# TeensyServoController.net
KiCad netlist of a schematic drawn in EAGLE
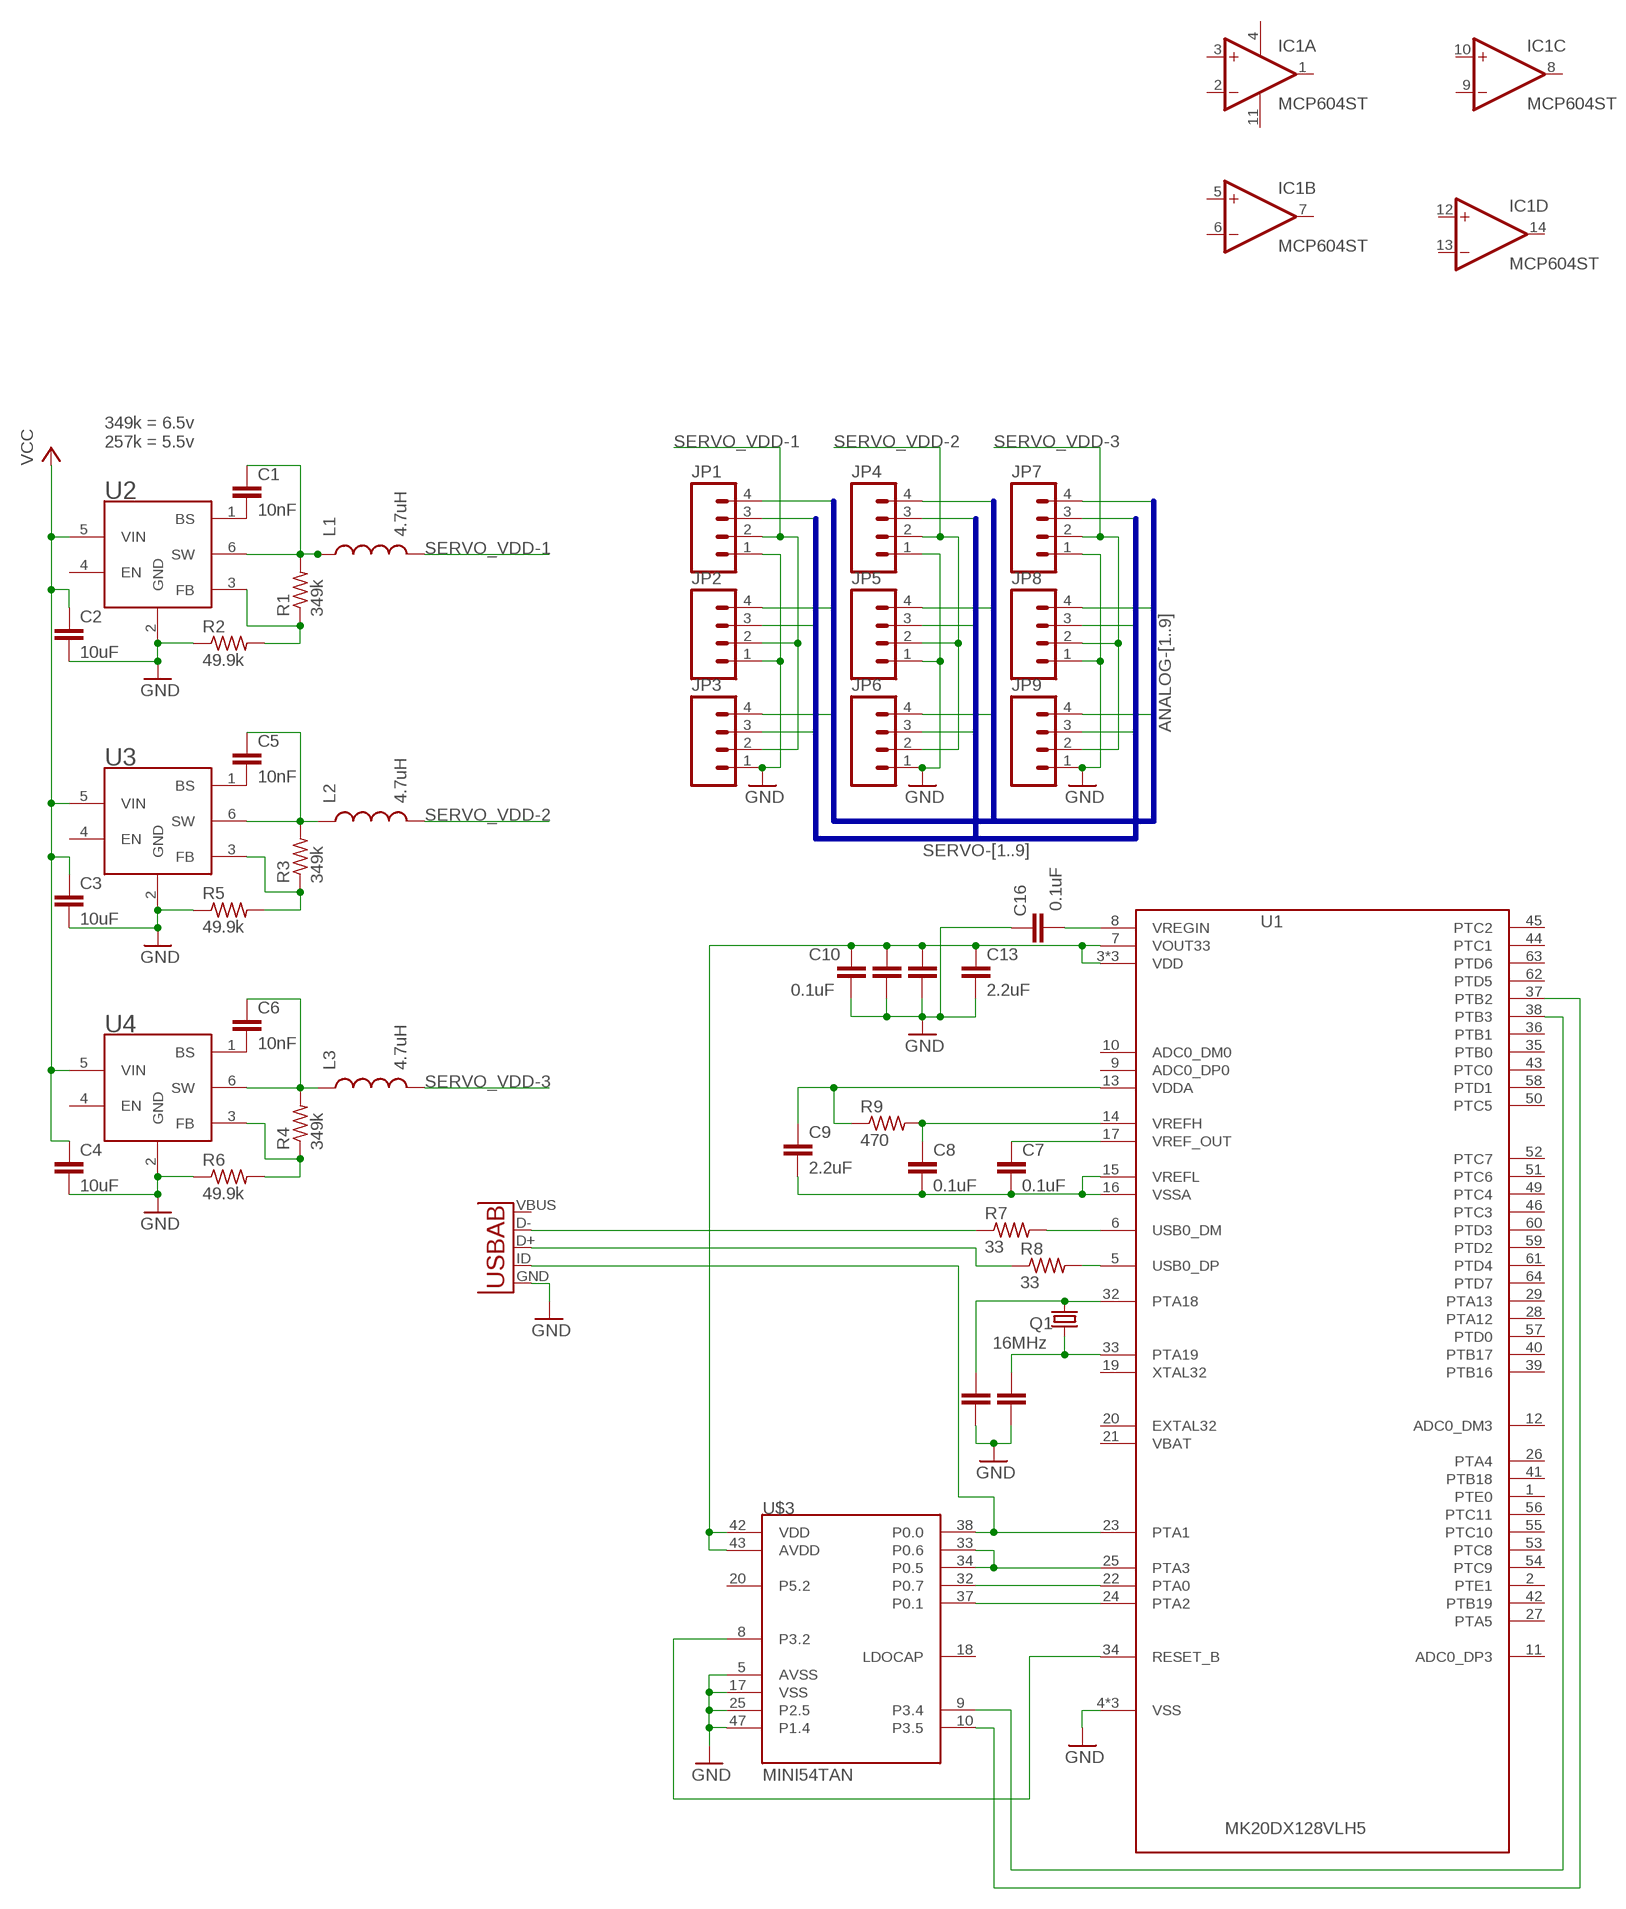
[diagram p0: schematic, sheet 1]

(export (version "E")
  (design (tool "Eeschema 10.0.6"))
  (components
    (comp (ref "C1")
      (value "10nF")
      (footprint "eagle-import:C0402")
      (libsource (lib "eagle-import") (part "C-EUC0402"))
    )
    (comp (ref "C2")
      (value "10uF")
      (footprint "eagle-import:C0805")
      (libsource (lib "eagle-import") (part "C-EUC0805"))
    )
    (comp (ref "C3")
      (value "10uF")
      (footprint "eagle-import:C0805")
      (libsource (lib "eagle-import") (part "C-EUC0805"))
    )
    (comp (ref "C4")
      (value "10uF")
      (footprint "eagle-import:C0805")
      (libsource (lib "eagle-import") (part "C-EUC0805"))
    )
    (comp (ref "C5")
      (value "10nF")
      (footprint "eagle-import:C0402")
      (libsource (lib "eagle-import") (part "C-EUC0402"))
    )
    (comp (ref "C6")
      (value "10nF")
      (footprint "eagle-import:C0402")
      (libsource (lib "eagle-import") (part "C-EUC0402"))
    )
    (comp (ref "C7")
      (value "0.1uF")
      (footprint "eagle-import:C0402")
      (libsource (lib "eagle-import") (part "C-EUC0402"))
    )
    (comp (ref "C8")
      (value "0.1uF")
      (footprint "eagle-import:C0402")
      (libsource (lib "eagle-import") (part "C-EUC0402"))
    )
    (comp (ref "C9")
      (value "2.2uF")
      (footprint "eagle-import:C0603")
      (libsource (lib "eagle-import") (part "C-EUC0603"))
    )
    (comp (ref "C10")
      (value "0.1uF")
      (footprint "eagle-import:C0402")
      (libsource (lib "eagle-import") (part "C-EUC0402"))
    )
    (comp (ref "C11")
      (value "0.1uF")
      (footprint "eagle-import:C0402")
      (libsource (lib "eagle-import") (part "C-EUC0402"))
    )
    (comp (ref "C12")
      (value "0.1uF")
      (footprint "eagle-import:C0402")
      (libsource (lib "eagle-import") (part "C-EUC0402"))
    )
    (comp (ref "C13")
      (value "2.2uF")
      (footprint "eagle-import:C0603")
      (libsource (lib "eagle-import") (part "C-EUC0603"))
    )
    (comp (ref "C14")
      (value "0.1uF")
      (footprint "eagle-import:C0402")
      (libsource (lib "eagle-import") (part "C-EUC0402"))
    )
    (comp (ref "C15")
      (value "0.1uF")
      (footprint "eagle-import:C0402")
      (libsource (lib "eagle-import") (part "C-EUC0402"))
    )
    (comp (ref "C16")
      (value "0.1uF")
      (footprint "eagle-import:C0402")
      (libsource (lib "eagle-import") (part "C-EUC0402"))
    )
    (comp (ref "IC1")
      (value "MCP604ST")
      (footprint "eagle-import:TSSOP14")
      (libsource (lib "eagle-import") (part "MCP604ST"))
    )
    (comp (ref "JP1")
      (value "M04LOCK")
      (footprint "eagle-import:1X04_LOCK")
      (libsource (lib "eagle-import") (part "M04LOCK"))
    )
    (comp (ref "JP2")
      (value "M04LOCK")
      (footprint "eagle-import:1X04_LOCK")
      (libsource (lib "eagle-import") (part "M04LOCK"))
    )
    (comp (ref "JP3")
      (value "M04LOCK")
      (footprint "eagle-import:1X04_LOCK")
      (libsource (lib "eagle-import") (part "M04LOCK"))
    )
    (comp (ref "JP4")
      (value "M04LOCK")
      (footprint "eagle-import:1X04_LOCK")
      (libsource (lib "eagle-import") (part "M04LOCK"))
    )
    (comp (ref "JP5")
      (value "M04LOCK")
      (footprint "eagle-import:1X04_LOCK")
      (libsource (lib "eagle-import") (part "M04LOCK"))
    )
    (comp (ref "JP6")
      (value "M04LOCK")
      (footprint "eagle-import:1X04_LOCK")
      (libsource (lib "eagle-import") (part "M04LOCK"))
    )
    (comp (ref "JP7")
      (value "M04LOCK")
      (footprint "eagle-import:1X04_LOCK")
      (libsource (lib "eagle-import") (part "M04LOCK"))
    )
    (comp (ref "JP8")
      (value "M04LOCK")
      (footprint "eagle-import:1X04_LOCK")
      (libsource (lib "eagle-import") (part "M04LOCK"))
    )
    (comp (ref "JP9")
      (value "M04LOCK")
      (footprint "eagle-import:1X04_LOCK")
      (libsource (lib "eagle-import") (part "M04LOCK"))
    )
    (comp (ref "L1")
      (value "4.7uH")
      (footprint "eagle-import:CR75")
      (libsource (lib "eagle-import") (part "INDUCTORCR75"))
    )
    (comp (ref "L2")
      (value "4.7uH")
      (footprint "eagle-import:CR75")
      (libsource (lib "eagle-import") (part "INDUCTORCR75"))
    )
    (comp (ref "L3")
      (value "4.7uH")
      (footprint "eagle-import:CR75")
      (libsource (lib "eagle-import") (part "INDUCTORCR75"))
    )
    (comp (ref "Q1")
      (value "16MHz")
      (footprint "eagle-import:CTS406")
      (libsource (lib "eagle-import") (part "CRYSTALCTS406"))
    )
    (comp (ref "R1")
      (value "349k")
      (footprint "eagle-import:R0402")
      (libsource (lib "eagle-import") (part "R-US_R0402"))
    )
    (comp (ref "R2")
      (value "49.9k")
      (footprint "eagle-import:R0402")
      (libsource (lib "eagle-import") (part "R-US_R0402"))
    )
    (comp (ref "R3")
      (value "349k")
      (footprint "eagle-import:R0402")
      (libsource (lib "eagle-import") (part "R-US_R0402"))
    )
    (comp (ref "R4")
      (value "349k")
      (footprint "eagle-import:R0402")
      (libsource (lib "eagle-import") (part "R-US_R0402"))
    )
    (comp (ref "R5")
      (value "49.9k")
      (footprint "eagle-import:R0402")
      (libsource (lib "eagle-import") (part "R-US_R0402"))
    )
    (comp (ref "R6")
      (value "49.9k")
      (footprint "eagle-import:R0402")
      (libsource (lib "eagle-import") (part "R-US_R0402"))
    )
    (comp (ref "R7")
      (value "33")
      (footprint "eagle-import:R0402")
      (libsource (lib "eagle-import") (part "R-US_R0402"))
    )
    (comp (ref "R8")
      (value "33")
      (footprint "eagle-import:R0402")
      (libsource (lib "eagle-import") (part "R-US_R0402"))
    )
    (comp (ref "R9")
      (value "470")
      (footprint "eagle-import:R0402")
      (libsource (lib "eagle-import") (part "R-US_R0402"))
    )
    (comp (ref "U$3")
      (value "MINI54TAN")
      (footprint "eagle-import:MINI54TAN")
      (libsource (lib "eagle-import") (part "MINI54TAN"))
    )
    (comp (ref "U1")
      (value "MK20DX128VLH5")
      (footprint "eagle-import:MK20DX128VLH5")
      (libsource (lib "eagle-import") (part "MK20DX128VLH5"))
    )
    (comp (ref "U2")
      (value "AP3211_SWITCHING_REGULATOR")
      (footprint "eagle-import:SOT-23-6")
      (libsource (lib "eagle-import") (part "AP3211_SWITCHING_REGULATOR"))
    )
    (comp (ref "U3")
      (value "AP3211_SWITCHING_REGULATOR")
      (footprint "eagle-import:SOT-23-6")
      (libsource (lib "eagle-import") (part "AP3211_SWITCHING_REGULATOR"))
    )
    (comp (ref "U4")
      (value "AP3211_SWITCHING_REGULATOR")
      (footprint "eagle-import:SOT-23-6")
      (libsource (lib "eagle-import") (part "AP3211_SWITCHING_REGULATOR"))
    )
    (comp (ref "U5")
      (value "USB-AB")
      (footprint "eagle-import:USB-AB-MICRO-SMD")
      (libsource (lib "eagle-import") (part "USB-AB"))
    )
  )
  (nets
    (net (code "21") (name "/SERVO_VDD-1") (class "Default")
      (node (ref "JP1") (pin "2") (pinfunction "2_2") (pintype "passive"))
      (node (ref "JP2") (pin "2") (pinfunction "2_2") (pintype "passive"))
      (node (ref "JP3") (pin "2") (pinfunction "2_2") (pintype "passive"))
      (node (ref "L1") (pin "P$2") (pinfunction "2_P$2") (pintype "passive"))
    )
    (net (code "22") (name "/SERVO_VDD-2") (class "Default")
      (node (ref "JP4") (pin "2") (pinfunction "2_2") (pintype "passive"))
      (node (ref "JP5") (pin "2") (pinfunction "2_2") (pintype "passive"))
      (node (ref "JP6") (pin "2") (pinfunction "2_2") (pintype "passive"))
      (node (ref "L2") (pin "P$2") (pinfunction "2_P$2") (pintype "passive"))
    )
    (net (code "23") (name "/SERVO_VDD-3") (class "Default")
      (node (ref "JP7") (pin "2") (pinfunction "2_2") (pintype "passive"))
      (node (ref "JP8") (pin "2") (pinfunction "2_2") (pintype "passive"))
      (node (ref "JP9") (pin "2") (pinfunction "2_2") (pintype "passive"))
      (node (ref "L3") (pin "P$2") (pinfunction "2_P$2") (pintype "passive"))
    )
    (net (code "24") (name "/V+") (class "Default")
      (node (ref "IC1") (pin "4") (pinfunction "V+_4") (pintype "power_in"))
    )
    (net (code "25") (name "/V-") (class "Default")
      (node (ref "IC1") (pin "11") (pinfunction "V-_11") (pintype "power_in"))
    )
    (net (code "26") (name "GND") (class "Default")
      (node (ref "C10") (pin "2") (pinfunction "2_2") (pintype "passive"))
      (node (ref "C11") (pin "2") (pinfunction "2_2") (pintype "passive"))
      (node (ref "C12") (pin "2") (pinfunction "2_2") (pintype "passive"))
      (node (ref "C13") (pin "2") (pinfunction "2_2") (pintype "passive"))
      (node (ref "C14") (pin "2") (pinfunction "2_2") (pintype "passive"))
      (node (ref "C15") (pin "2") (pinfunction "2_2") (pintype "passive"))
      (node (ref "C16") (pin "1") (pinfunction "1_1") (pintype "passive"))
      (node (ref "C2") (pin "2") (pinfunction "2_2") (pintype "passive"))
      (node (ref "C3") (pin "2") (pinfunction "2_2") (pintype "passive"))
      (node (ref "C4") (pin "2") (pinfunction "2_2") (pintype "passive"))
      (node (ref "JP1") (pin "1") (pinfunction "1_1") (pintype "passive"))
      (node (ref "JP2") (pin "1") (pinfunction "1_1") (pintype "passive"))
      (node (ref "JP3") (pin "1") (pinfunction "1_1") (pintype "passive"))
      (node (ref "JP4") (pin "1") (pinfunction "1_1") (pintype "passive"))
      (node (ref "JP5") (pin "1") (pinfunction "1_1") (pintype "passive"))
      (node (ref "JP6") (pin "1") (pinfunction "1_1") (pintype "passive"))
      (node (ref "JP7") (pin "1") (pinfunction "1_1") (pintype "passive"))
      (node (ref "JP8") (pin "1") (pinfunction "1_1") (pintype "passive"))
      (node (ref "JP9") (pin "1") (pinfunction "1_1") (pintype "passive"))
      (node (ref "R2") (pin "1") (pinfunction "1_1") (pintype "passive"))
      (node (ref "R5") (pin "1") (pinfunction "1_1") (pintype "passive"))
      (node (ref "R6") (pin "1") (pinfunction "1_1") (pintype "passive"))
      (node (ref "U$3") (pin "17") (pinfunction "VSS_17") (pintype "bidirectional"))
      (node (ref "U$3") (pin "25") (pinfunction "P2.5_25") (pintype "bidirectional"))
      (node (ref "U$3") (pin "47") (pinfunction "P1.4_47") (pintype "bidirectional"))
      (node (ref "U$3") (pin "5") (pinfunction "AVSS_5") (pintype "bidirectional"))
      (node (ref "U1") (pin "31") (pinfunction "VSS_31") (pintype "bidirectional"))
      (node (ref "U1") (pin "4") (pinfunction "VSS_4") (pintype "bidirectional"))
      (node (ref "U1") (pin "47") (pinfunction "VSS_47") (pintype "bidirectional"))
      (node (ref "U2") (pin "2") (pinfunction "GND_2") (pintype "bidirectional"))
      (node (ref "U3") (pin "2") (pinfunction "GND_2") (pintype "bidirectional"))
      (node (ref "U4") (pin "2") (pinfunction "GND_2") (pintype "bidirectional"))
      (node (ref "U5") (pin "GND") (pinfunction "GND_GND") (pintype "bidirectional"))
    )
    (net (code "27") (name "Net-(L1-1)") (class "Default")
      (node (ref "C1") (pin "1") (pinfunction "1_1") (pintype "passive"))
      (node (ref "L1") (pin "P$1") (pinfunction "1_P$1") (pintype "passive"))
      (node (ref "R1") (pin "2") (pinfunction "2_2") (pintype "passive"))
      (node (ref "U2") (pin "6") (pinfunction "SW_6") (pintype "bidirectional"))
    )
    (net (code "28") (name "Net-(L2-1)") (class "Default")
      (node (ref "C5") (pin "1") (pinfunction "1_1") (pintype "passive"))
      (node (ref "L2") (pin "P$1") (pinfunction "1_P$1") (pintype "passive"))
      (node (ref "R3") (pin "2") (pinfunction "2_2") (pintype "passive"))
      (node (ref "U3") (pin "6") (pinfunction "SW_6") (pintype "bidirectional"))
    )
    (net (code "29") (name "Net-(L3-1)") (class "Default")
      (node (ref "C6") (pin "1") (pinfunction "1_1") (pintype "passive"))
      (node (ref "L3") (pin "P$1") (pinfunction "1_P$1") (pintype "passive"))
      (node (ref "R4") (pin "2") (pinfunction "2_2") (pintype "passive"))
      (node (ref "U4") (pin "6") (pinfunction "SW_6") (pintype "bidirectional"))
    )
    (net (code "30") (name "Net-(Q1-2)") (class "Default")
      (node (ref "C14") (pin "1") (pinfunction "1_1") (pintype "passive"))
      (node (ref "Q1") (pin "3") (pinfunction "2_3") (pintype "passive"))
      (node (ref "U1") (pin "32") (pinfunction "PTA18_32") (pintype "bidirectional"))
    )
    (net (code "31") (name "Net-(R7-Pad1)") (class "Default")
      (node (ref "R7") (pin "1") (pinfunction "1_1") (pintype "passive"))
      (node (ref "U5") (pin "D-") (pinfunction "D-_D-") (pintype "bidirectional"))
    )
    (net (code "32") (name "Net-(R8-Pad1)") (class "Default")
      (node (ref "R8") (pin "1") (pinfunction "1_1") (pintype "passive"))
      (node (ref "U5") (pin "D+") (pinfunction "D+_D+") (pintype "bidirectional"))
    )
    (net (code "33") (name "Net-(U$3-AVDD)") (class "Default")
      (node (ref "C10") (pin "1") (pinfunction "1_1") (pintype "passive"))
      (node (ref "C11") (pin "1") (pinfunction "1_1") (pintype "passive"))
      (node (ref "C12") (pin "1") (pinfunction "1_1") (pintype "passive"))
      (node (ref "C13") (pin "1") (pinfunction "1_1") (pintype "passive"))
      (node (ref "U$3") (pin "42") (pinfunction "VDD_42") (pintype "bidirectional"))
      (node (ref "U$3") (pin "43") (pinfunction "AVDD_43") (pintype "bidirectional"))
      (node (ref "U1") (pin "3") (pinfunction "VDD_3") (pintype "bidirectional"))
      (node (ref "U1") (pin "30") (pinfunction "VDD_30") (pintype "bidirectional"))
      (node (ref "U1") (pin "48") (pinfunction "VDD_48") (pintype "bidirectional"))
      (node (ref "U1") (pin "7") (pinfunction "VOUT33_7") (pintype "bidirectional"))
    )
    (net (code "34") (name "Net-(U$3-P0.0)") (class "Default")
      (node (ref "U$3") (pin "38") (pinfunction "P0.0_38") (pintype "bidirectional"))
      (node (ref "U1") (pin "23") (pinfunction "PTA1_23") (pintype "bidirectional"))
      (node (ref "U5") (pin "ID") (pinfunction "USBID_ID") (pintype "bidirectional"))
    )
    (net (code "35") (name "Net-(U$3-P0.1)") (class "Default")
      (node (ref "U$3") (pin "37") (pinfunction "P0.1_37") (pintype "bidirectional"))
      (node (ref "U1") (pin "24") (pinfunction "PTA2_24") (pintype "bidirectional"))
    )
    (net (code "36") (name "Net-(U$3-P0.5)") (class "Default")
      (node (ref "U$3") (pin "33") (pinfunction "P0.6_33") (pintype "bidirectional"))
      (node (ref "U$3") (pin "34") (pinfunction "P0.5_34") (pintype "bidirectional"))
      (node (ref "U1") (pin "25") (pinfunction "PTA3_25") (pintype "bidirectional"))
    )
    (net (code "37") (name "Net-(U$3-P0.7)") (class "Default")
      (node (ref "U$3") (pin "32") (pinfunction "P0.7_32") (pintype "bidirectional"))
      (node (ref "U1") (pin "22") (pinfunction "PTA0_22") (pintype "bidirectional"))
    )
    (net (code "38") (name "Net-(U$3-P3.2)") (class "Default")
      (node (ref "U$3") (pin "8") (pinfunction "P3.2_8") (pintype "bidirectional"))
      (node (ref "U1") (pin "34") (pinfunction "RESET_B_34") (pintype "bidirectional"))
    )
    (net (code "39") (name "Net-(U$3-P3.4)") (class "Default")
      (node (ref "U$3") (pin "9") (pinfunction "P3.4_9") (pintype "bidirectional"))
      (node (ref "U1") (pin "38") (pinfunction "PTB3_38") (pintype "bidirectional"))
    )
    (net (code "40") (name "Net-(U$3-P3.5)") (class "Default")
      (node (ref "U$3") (pin "10") (pinfunction "P3.5_10") (pintype "bidirectional"))
      (node (ref "U1") (pin "37") (pinfunction "PTB2_37") (pintype "bidirectional"))
    )
    (net (code "41") (name "Net-(U1-PTA19)") (class "Default")
      (node (ref "C15") (pin "1") (pinfunction "1_1") (pintype "passive"))
      (node (ref "Q1") (pin "1") (pinfunction "1_1") (pintype "passive"))
      (node (ref "U1") (pin "33") (pinfunction "PTA19_33") (pintype "bidirectional"))
    )
    (net (code "42") (name "Net-(U1-USB0_DM)") (class "Default")
      (node (ref "R7") (pin "2") (pinfunction "2_2") (pintype "passive"))
      (node (ref "U1") (pin "6") (pinfunction "USB0_DM_6") (pintype "bidirectional"))
    )
    (net (code "43") (name "Net-(U1-USB0_DP)") (class "Default")
      (node (ref "R8") (pin "2") (pinfunction "2_2") (pintype "passive"))
      (node (ref "U1") (pin "5") (pinfunction "USB0_DP_5") (pintype "bidirectional"))
    )
    (net (code "44") (name "Net-(U1-VDDA)") (class "Default")
      (node (ref "C9") (pin "1") (pinfunction "1_1") (pintype "passive"))
      (node (ref "R9") (pin "1") (pinfunction "1_1") (pintype "passive"))
      (node (ref "U1") (pin "13") (pinfunction "VDDA_13") (pintype "bidirectional"))
    )
    (net (code "45") (name "Net-(U1-VREFH)") (class "Default")
      (node (ref "C8") (pin "1") (pinfunction "1_1") (pintype "passive"))
      (node (ref "R9") (pin "2") (pinfunction "2_2") (pintype "passive"))
      (node (ref "U1") (pin "14") (pinfunction "VREFH_14") (pintype "bidirectional"))
    )
    (net (code "46") (name "Net-(U1-VREFL)") (class "Default")
      (node (ref "C7") (pin "2") (pinfunction "2_2") (pintype "passive"))
      (node (ref "C8") (pin "2") (pinfunction "2_2") (pintype "passive"))
      (node (ref "C9") (pin "2") (pinfunction "2_2") (pintype "passive"))
      (node (ref "U1") (pin "15") (pinfunction "VREFL_15") (pintype "bidirectional"))
      (node (ref "U1") (pin "16") (pinfunction "VSSA_16") (pintype "bidirectional"))
    )
    (net (code "47") (name "Net-(U1-VREF_OUT)") (class "Default")
      (node (ref "C7") (pin "1") (pinfunction "1_1") (pintype "passive"))
      (node (ref "U1") (pin "17") (pinfunction "VREF_OUT_17") (pintype "bidirectional"))
    )
    (net (code "48") (name "Net-(U1-VREGIN)") (class "Default")
      (node (ref "C16") (pin "2") (pinfunction "2_2") (pintype "passive"))
      (node (ref "U1") (pin "8") (pinfunction "VREGIN_8") (pintype "bidirectional"))
    )
    (net (code "49") (name "Net-(U2-BS)") (class "Default")
      (node (ref "C1") (pin "2") (pinfunction "2_2") (pintype "passive"))
      (node (ref "U2") (pin "1") (pinfunction "BS_1") (pintype "bidirectional"))
    )
    (net (code "50") (name "Net-(U2-FB)") (class "Default")
      (node (ref "R1") (pin "1") (pinfunction "1_1") (pintype "passive"))
      (node (ref "R2") (pin "2") (pinfunction "2_2") (pintype "passive"))
      (node (ref "U2") (pin "3") (pinfunction "FB_3") (pintype "bidirectional"))
    )
    (net (code "51") (name "Net-(U3-BS)") (class "Default")
      (node (ref "C5") (pin "2") (pinfunction "2_2") (pintype "passive"))
      (node (ref "U3") (pin "1") (pinfunction "BS_1") (pintype "bidirectional"))
    )
    (net (code "52") (name "Net-(U3-FB)") (class "Default")
      (node (ref "R3") (pin "1") (pinfunction "1_1") (pintype "passive"))
      (node (ref "R5") (pin "2") (pinfunction "2_2") (pintype "passive"))
      (node (ref "U3") (pin "3") (pinfunction "FB_3") (pintype "bidirectional"))
    )
    (net (code "53") (name "Net-(U4-BS)") (class "Default")
      (node (ref "C6") (pin "2") (pinfunction "2_2") (pintype "passive"))
      (node (ref "U4") (pin "1") (pinfunction "BS_1") (pintype "bidirectional"))
    )
    (net (code "54") (name "Net-(U4-FB)") (class "Default")
      (node (ref "R4") (pin "1") (pinfunction "1_1") (pintype "passive"))
      (node (ref "R6") (pin "2") (pinfunction "2_2") (pintype "passive"))
      (node (ref "U4") (pin "3") (pinfunction "FB_3") (pintype "bidirectional"))
    )
    (net (code "55") (name "VCC") (class "Default")
      (node (ref "C2") (pin "1") (pinfunction "1_1") (pintype "passive"))
      (node (ref "C3") (pin "1") (pinfunction "1_1") (pintype "passive"))
      (node (ref "C4") (pin "1") (pinfunction "1_1") (pintype "passive"))
      (node (ref "U2") (pin "5") (pinfunction "VIN_5") (pintype "bidirectional"))
      (node (ref "U3") (pin "5") (pinfunction "VIN_5") (pintype "bidirectional"))
      (node (ref "U4") (pin "5") (pinfunction "VIN_5") (pintype "bidirectional"))
    )
    (net (code "56") (name "unconnected-(IC1A-+IN-Pad3)") (class "Default")
      (node (ref "IC1") (pin "3") (pinfunction "+IN_3") (pintype "input"))
    )
    (net (code "57") (name "unconnected-(IC1A--IN-Pad2)") (class "Default")
      (node (ref "IC1") (pin "2") (pinfunction "-IN_2") (pintype "input"))
    )
    (net (code "58") (name "unconnected-(IC1A-OUT-Pad1)") (class "Default")
      (node (ref "IC1") (pin "1") (pinfunction "OUT_1") (pintype "output"))
    )
    (net (code "59") (name "unconnected-(IC1B-+IN-Pad5)") (class "Default")
      (node (ref "IC1") (pin "5") (pinfunction "+IN_5") (pintype "input"))
    )
    (net (code "60") (name "unconnected-(IC1B--IN-Pad6)") (class "Default")
      (node (ref "IC1") (pin "6") (pinfunction "-IN_6") (pintype "input"))
    )
    (net (code "61") (name "unconnected-(IC1B-OUT-Pad7)") (class "Default")
      (node (ref "IC1") (pin "7") (pinfunction "OUT_7") (pintype "output"))
    )
    (net (code "62") (name "unconnected-(IC1C-+IN-Pad10)") (class "Default")
      (node (ref "IC1") (pin "10") (pinfunction "+IN_10") (pintype "input"))
    )
    (net (code "63") (name "unconnected-(IC1C--IN-Pad9)") (class "Default")
      (node (ref "IC1") (pin "9") (pinfunction "-IN_9") (pintype "input"))
    )
    (net (code "64") (name "unconnected-(IC1C-OUT-Pad8)") (class "Default")
      (node (ref "IC1") (pin "8") (pinfunction "OUT_8") (pintype "output"))
    )
    (net (code "65") (name "unconnected-(IC1D-+IN-Pad12)") (class "Default")
      (node (ref "IC1") (pin "12") (pinfunction "+IN_12") (pintype "input"))
    )
    (net (code "66") (name "unconnected-(IC1D--IN-Pad13)") (class "Default")
      (node (ref "IC1") (pin "13") (pinfunction "-IN_13") (pintype "input"))
    )
    (net (code "67") (name "unconnected-(IC1D-OUT-Pad14)") (class "Default")
      (node (ref "IC1") (pin "14") (pinfunction "OUT_14") (pintype "output"))
    )
    (net (code "68") (name "unconnected-(JP1-Pad3)") (class "Default")
      (node (ref "JP1") (pin "3") (pinfunction "3_3") (pintype "passive"))
    )
    (net (code "69") (name "unconnected-(JP1-Pad4)") (class "Default")
      (node (ref "JP1") (pin "4") (pinfunction "4_4") (pintype "passive"))
    )
    (net (code "70") (name "unconnected-(JP2-Pad3)") (class "Default")
      (node (ref "JP2") (pin "3") (pinfunction "3_3") (pintype "passive"))
    )
    (net (code "71") (name "unconnected-(JP2-Pad4)") (class "Default")
      (node (ref "JP2") (pin "4") (pinfunction "4_4") (pintype "passive"))
    )
    (net (code "72") (name "unconnected-(JP3-Pad3)") (class "Default")
      (node (ref "JP3") (pin "3") (pinfunction "3_3") (pintype "passive"))
    )
    (net (code "73") (name "unconnected-(JP3-Pad4)") (class "Default")
      (node (ref "JP3") (pin "4") (pinfunction "4_4") (pintype "passive"))
    )
    (net (code "74") (name "unconnected-(JP4-Pad3)") (class "Default")
      (node (ref "JP4") (pin "3") (pinfunction "3_3") (pintype "passive"))
    )
    (net (code "75") (name "unconnected-(JP4-Pad4)") (class "Default")
      (node (ref "JP4") (pin "4") (pinfunction "4_4") (pintype "passive"))
    )
    (net (code "76") (name "unconnected-(JP5-Pad3)") (class "Default")
      (node (ref "JP5") (pin "3") (pinfunction "3_3") (pintype "passive"))
    )
    (net (code "77") (name "unconnected-(JP5-Pad4)") (class "Default")
      (node (ref "JP5") (pin "4") (pinfunction "4_4") (pintype "passive"))
    )
    (net (code "78") (name "unconnected-(JP6-Pad3)") (class "Default")
      (node (ref "JP6") (pin "3") (pinfunction "3_3") (pintype "passive"))
    )
    (net (code "79") (name "unconnected-(JP6-Pad4)") (class "Default")
      (node (ref "JP6") (pin "4") (pinfunction "4_4") (pintype "passive"))
    )
    (net (code "80") (name "unconnected-(JP7-Pad3)") (class "Default")
      (node (ref "JP7") (pin "3") (pinfunction "3_3") (pintype "passive"))
    )
    (net (code "81") (name "unconnected-(JP7-Pad4)") (class "Default")
      (node (ref "JP7") (pin "4") (pinfunction "4_4") (pintype "passive"))
    )
    (net (code "82") (name "unconnected-(JP8-Pad3)") (class "Default")
      (node (ref "JP8") (pin "3") (pinfunction "3_3") (pintype "passive"))
    )
    (net (code "83") (name "unconnected-(JP8-Pad4)") (class "Default")
      (node (ref "JP8") (pin "4") (pinfunction "4_4") (pintype "passive"))
    )
    (net (code "84") (name "unconnected-(JP9-Pad3)") (class "Default")
      (node (ref "JP9") (pin "3") (pinfunction "3_3") (pintype "passive"))
    )
    (net (code "85") (name "unconnected-(JP9-Pad4)") (class "Default")
      (node (ref "JP9") (pin "4") (pinfunction "4_4") (pintype "passive"))
    )
    (net (code "86") (name "unconnected-(U$3-LDOCAP-Pad18)") (class "Default")
      (node (ref "U$3") (pin "18") (pinfunction "LDOCAP_18") (pintype "bidirectional"))
    )
    (net (code "87") (name "unconnected-(U$3-P5.2-Pad20)") (class "Default")
      (node (ref "U$3") (pin "20") (pinfunction "P5.2_20") (pintype "bidirectional"))
    )
    (net (code "88") (name "unconnected-(U1-ADC0_DM0-Pad10)") (class "Default")
      (node (ref "U1") (pin "10") (pinfunction "ADC0_DM0_10") (pintype "bidirectional"))
    )
    (net (code "89") (name "unconnected-(U1-ADC0_DM3-Pad12)") (class "Default")
      (node (ref "U1") (pin "12") (pinfunction "ADC0_DM3_12") (pintype "bidirectional"))
    )
    (net (code "90") (name "unconnected-(U1-ADC0_DP0-Pad9)") (class "Default")
      (node (ref "U1") (pin "9") (pinfunction "ADC0_DP0_9") (pintype "bidirectional"))
    )
    (net (code "91") (name "unconnected-(U1-ADC0_DP3-Pad11)") (class "Default")
      (node (ref "U1") (pin "11") (pinfunction "ADC0_DP3_11") (pintype "bidirectional"))
    )
    (net (code "92") (name "unconnected-(U1-EXTAL32-Pad20)") (class "Default")
      (node (ref "U1") (pin "20") (pinfunction "EXTAL32_20") (pintype "bidirectional"))
    )
    (net (code "93") (name "unconnected-(U1-PTA4-Pad26)") (class "Default")
      (node (ref "U1") (pin "26") (pinfunction "PTA4_26") (pintype "bidirectional"))
    )
    (net (code "94") (name "unconnected-(U1-PTA5-Pad27)") (class "Default")
      (node (ref "U1") (pin "27") (pinfunction "PTA5_27") (pintype "bidirectional"))
    )
    (net (code "95") (name "unconnected-(U1-PTA12-Pad28)") (class "Default")
      (node (ref "U1") (pin "28") (pinfunction "PTA12_28") (pintype "bidirectional"))
    )
    (net (code "96") (name "unconnected-(U1-PTA13-Pad29)") (class "Default")
      (node (ref "U1") (pin "29") (pinfunction "PTA13_29") (pintype "bidirectional"))
    )
    (net (code "97") (name "unconnected-(U1-PTB0-Pad35)") (class "Default")
      (node (ref "U1") (pin "35") (pinfunction "PTB0_35") (pintype "bidirectional"))
    )
    (net (code "98") (name "unconnected-(U1-PTB1-Pad36)") (class "Default")
      (node (ref "U1") (pin "36") (pinfunction "PTB1_36") (pintype "bidirectional"))
    )
    (net (code "99") (name "unconnected-(U1-PTB16-Pad39)") (class "Default")
      (node (ref "U1") (pin "39") (pinfunction "PTB16_39") (pintype "bidirectional"))
    )
    (net (code "100") (name "unconnected-(U1-PTB17-Pad40)") (class "Default")
      (node (ref "U1") (pin "40") (pinfunction "PTB17_40") (pintype "bidirectional"))
    )
    (net (code "101") (name "unconnected-(U1-PTB18-Pad41)") (class "Default")
      (node (ref "U1") (pin "41") (pinfunction "PTB18_41") (pintype "bidirectional"))
    )
    (net (code "102") (name "unconnected-(U1-PTB19-Pad42)") (class "Default")
      (node (ref "U1") (pin "42") (pinfunction "PTB19_42") (pintype "bidirectional"))
    )
    (net (code "103") (name "unconnected-(U1-PTC0-Pad43)") (class "Default")
      (node (ref "U1") (pin "43") (pinfunction "PTC0_43") (pintype "bidirectional"))
    )
    (net (code "104") (name "unconnected-(U1-PTC1-Pad44)") (class "Default")
      (node (ref "U1") (pin "44") (pinfunction "PTC1_44") (pintype "bidirectional"))
    )
    (net (code "105") (name "unconnected-(U1-PTC2-Pad45)") (class "Default")
      (node (ref "U1") (pin "45") (pinfunction "PTC2_45") (pintype "bidirectional"))
    )
    (net (code "106") (name "unconnected-(U1-PTC3-Pad46)") (class "Default")
      (node (ref "U1") (pin "46") (pinfunction "PTC3_46") (pintype "bidirectional"))
    )
    (net (code "107") (name "unconnected-(U1-PTC4-Pad49)") (class "Default")
      (node (ref "U1") (pin "49") (pinfunction "PTC4_49") (pintype "bidirectional"))
    )
    (net (code "108") (name "unconnected-(U1-PTC5-Pad50)") (class "Default")
      (node (ref "U1") (pin "50") (pinfunction "PTC5_50") (pintype "bidirectional"))
    )
    (net (code "109") (name "unconnected-(U1-PTC6-Pad51)") (class "Default")
      (node (ref "U1") (pin "51") (pinfunction "PTC6_51") (pintype "bidirectional"))
    )
    (net (code "110") (name "unconnected-(U1-PTC7-Pad52)") (class "Default")
      (node (ref "U1") (pin "52") (pinfunction "PTC7_52") (pintype "bidirectional"))
    )
    (net (code "111") (name "unconnected-(U1-PTC8-Pad53)") (class "Default")
      (node (ref "U1") (pin "53") (pinfunction "PTC8_53") (pintype "bidirectional"))
    )
    (net (code "112") (name "unconnected-(U1-PTC9-Pad54)") (class "Default")
      (node (ref "U1") (pin "54") (pinfunction "PTC9_54") (pintype "bidirectional"))
    )
    (net (code "113") (name "unconnected-(U1-PTC10-Pad55)") (class "Default")
      (node (ref "U1") (pin "55") (pinfunction "PTC10_55") (pintype "bidirectional"))
    )
    (net (code "114") (name "unconnected-(U1-PTC11-Pad56)") (class "Default")
      (node (ref "U1") (pin "56") (pinfunction "PTC11_56") (pintype "bidirectional"))
    )
    (net (code "115") (name "unconnected-(U1-PTD0-Pad57)") (class "Default")
      (node (ref "U1") (pin "57") (pinfunction "PTD0_57") (pintype "bidirectional"))
    )
    (net (code "116") (name "unconnected-(U1-PTD1-Pad58)") (class "Default")
      (node (ref "U1") (pin "58") (pinfunction "PTD1_58") (pintype "bidirectional"))
    )
    (net (code "117") (name "unconnected-(U1-PTD2-Pad59)") (class "Default")
      (node (ref "U1") (pin "59") (pinfunction "PTD2_59") (pintype "bidirectional"))
    )
    (net (code "118") (name "unconnected-(U1-PTD3-Pad60)") (class "Default")
      (node (ref "U1") (pin "60") (pinfunction "PTD3_60") (pintype "bidirectional"))
    )
    (net (code "119") (name "unconnected-(U1-PTD4-Pad61)") (class "Default")
      (node (ref "U1") (pin "61") (pinfunction "PTD4_61") (pintype "bidirectional"))
    )
    (net (code "120") (name "unconnected-(U1-PTD5-Pad62)") (class "Default")
      (node (ref "U1") (pin "62") (pinfunction "PTD5_62") (pintype "bidirectional"))
    )
    (net (code "121") (name "unconnected-(U1-PTD6-Pad63)") (class "Default")
      (node (ref "U1") (pin "63") (pinfunction "PTD6_63") (pintype "bidirectional"))
    )
    (net (code "122") (name "unconnected-(U1-PTD7-Pad64)") (class "Default")
      (node (ref "U1") (pin "64") (pinfunction "PTD7_64") (pintype "bidirectional"))
    )
    (net (code "123") (name "unconnected-(U1-PTE0-Pad1)") (class "Default")
      (node (ref "U1") (pin "1") (pinfunction "PTE0_1") (pintype "bidirectional"))
    )
    (net (code "124") (name "unconnected-(U1-PTE1-Pad2)") (class "Default")
      (node (ref "U1") (pin "2") (pinfunction "PTE1_2") (pintype "bidirectional"))
    )
    (net (code "125") (name "unconnected-(U1-VBAT-Pad21)") (class "Default")
      (node (ref "U1") (pin "21") (pinfunction "VBAT_21") (pintype "bidirectional"))
    )
    (net (code "126") (name "unconnected-(U1-XTAL32-Pad19)") (class "Default")
      (node (ref "U1") (pin "19") (pinfunction "XTAL32_19") (pintype "bidirectional"))
    )
    (net (code "127") (name "unconnected-(U2-EN-Pad4)") (class "Default")
      (node (ref "U2") (pin "4") (pinfunction "EN_4") (pintype "bidirectional"))
    )
    (net (code "128") (name "unconnected-(U3-EN-Pad4)") (class "Default")
      (node (ref "U3") (pin "4") (pinfunction "EN_4") (pintype "bidirectional"))
    )
    (net (code "129") (name "unconnected-(U4-EN-Pad4)") (class "Default")
      (node (ref "U4") (pin "4") (pinfunction "EN_4") (pintype "bidirectional"))
    )
    (net (code "130") (name "unconnected-(U5-PadVBUS)") (class "Default")
      (node (ref "U5") (pin "VBUS") (pinfunction "VBUS_VBUS") (pintype "bidirectional"))
    )
  )
)
